# demo0920.net
KiCad netlist of a schematic drawn in Altium Designer
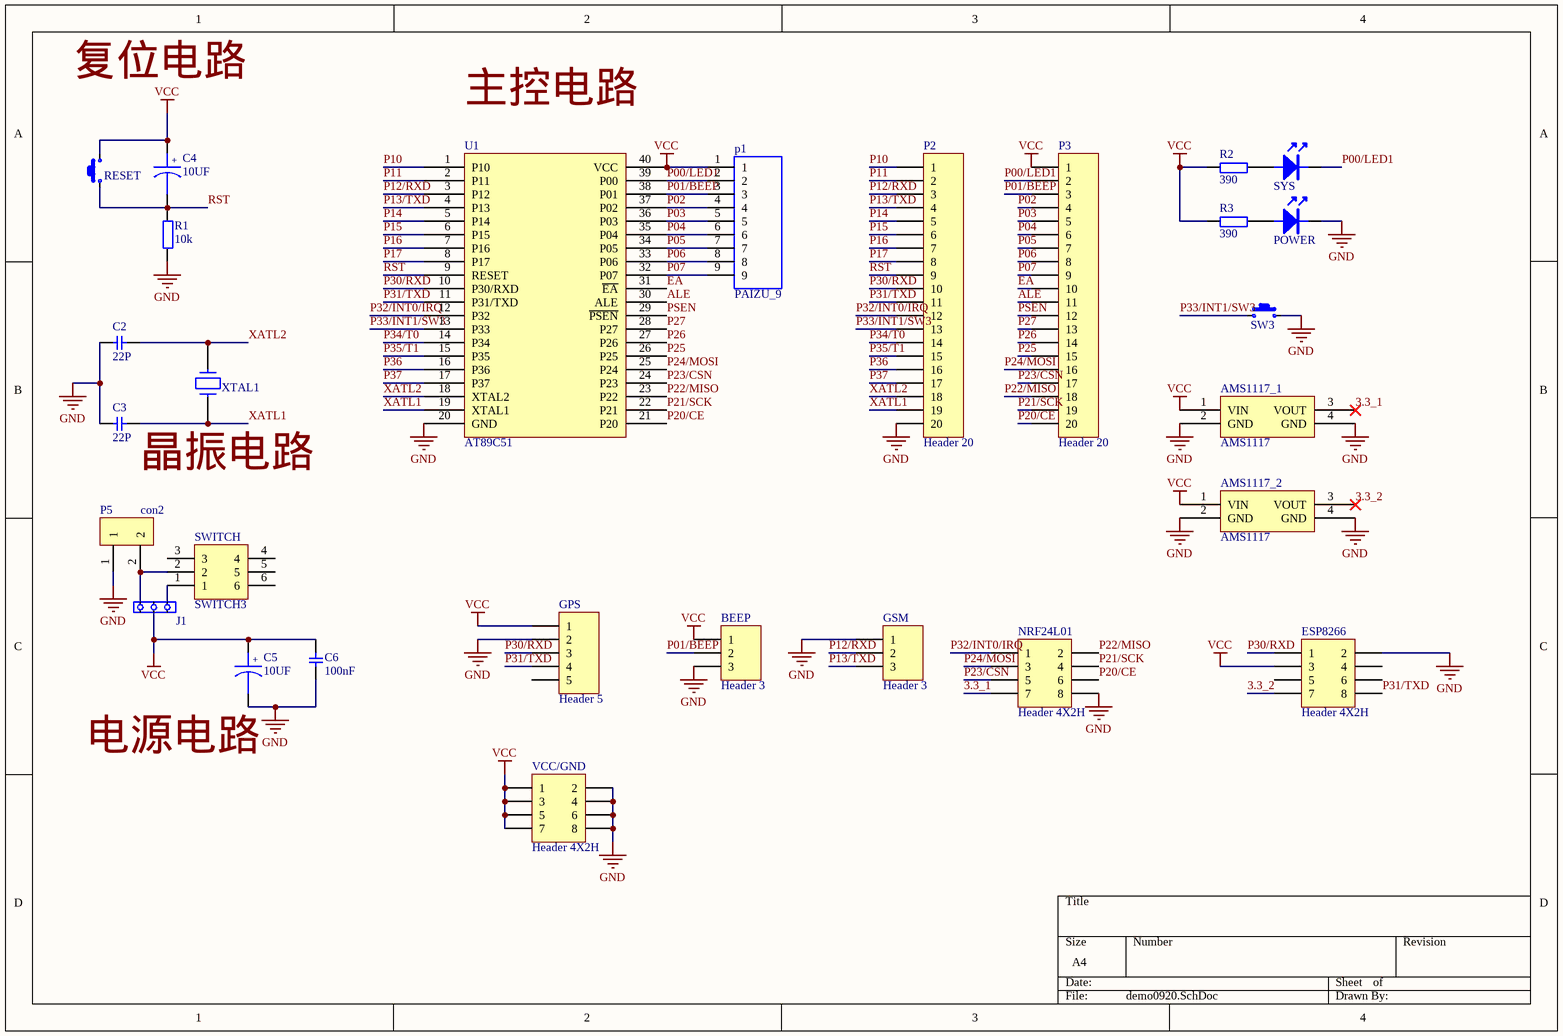
[diagram p0: demo0920.SchDoc]

(export (version "E")
  (design (tool "Eeschema 10.0.6"))
  (components
    (comp (ref "AMS1117_1") (value "AMS1117") (footprint "AMS1117") (libsource (lib "SQ-1") (part "AMS1117")))
    (comp (ref "AMS1117_2") (value "AMS1117") (footprint "AMS1117") (libsource (lib "SQ-1") (part "AMS1117")))
    (comp (ref "BEEP")
      (value "Header 3")
      (footprint "HDR1X3")
      (description "Header, 3-Pin")
      (fields (field (name "PUBLISHER") "Altium Limited"))
      (libsource (lib "Miscellaneous Connectors") (part "Header 3"))
    )
    (comp (ref "C2")
      (value "22")
      (footprint "0805C")
      (description "C")
      (fields (field (name "ALTIUM_UNNAMED_1") "22P"))
      (libsource (lib "SQ-1") (part "CAP"))
    )
    (comp (ref "C3")
      (value "22")
      (footprint "0805C")
      (description "C")
      (fields (field (name "ALTIUM_UNNAMED_1") "22P"))
      (libsource (lib "SQ-1") (part "CAP"))
    )
    (comp (ref "C4")
      (value "CAPD")
      (footprint "RB470U")
      (fields (field (name "ALTIUM_UNNAMED_1") "10UF"))
      (libsource (lib "SQ-1") (part "CAPD"))
    )
    (comp (ref "C5")
      (value "CAPD")
      (footprint "RB470U")
      (fields (field (name "ALTIUM_UNNAMED_1") "10UF"))
      (libsource (lib "SQ-1") (part "CAPD"))
    )
    (comp (ref "C6")
      (value "22")
      (footprint "0805C")
      (description "C")
      (fields (field (name "ALTIUM_UNNAMED_1") "100nF"))
      (libsource (lib "SQ-1") (part "CAP"))
    )
    (comp (ref "ESP8266")
      (value "Header 4X2H")
      (footprint "HDR2X4H")
      (description "Header, 4-Pin, Dual row, Right Angle")
      (fields (field (name "PUBLISHER") "Altium Limited"))
      (libsource (lib "SQ-1") (part "Header 4X2H"))
    )
    (comp (ref "GPS")
      (value "Header 5")
      (footprint "HDR1X5")
      (description "Header, 5-Pin")
      (fields (field (name "PUBLISHER") "Altium Limited"))
      (libsource (lib "Miscellaneous Connectors") (part "Header 5"))
    )
    (comp (ref "GSM")
      (value "Header 3")
      (footprint "HDR1X3")
      (description "Header, 3-Pin")
      (fields (field (name "PUBLISHER") "Altium Limited"))
      (libsource (lib "Miscellaneous Connectors") (part "Header 3"))
    )
    (comp (ref "J1") (value "Select") (footprint "CON3") (libsource (lib "SQ-1") (part "JUMP3")))
    (comp (ref "NRF24L01")
      (value "Header 4X2H")
      (footprint "HDR2X4H")
      (description "Header, 4-Pin, Dual row, Right Angle")
      (fields (field (name "PUBLISHER") "Altium Limited"))
      (libsource (lib "SQ-1") (part "Header 4X2H"))
    )
    (comp (ref "p1") (value "PAIZU_9") (footprint "PAIZU_9") (libsource (lib "SQ-1") (part "PAIZU_9")))
    (comp (ref "P2")
      (value "Header 20")
      (footprint "HDR1X20")
      (description "Header, 20-Pin")
      (fields (field (name "PUBLISHER") "Altium Limited"))
      (libsource (lib "SQ-1") (part "Header 20"))
    )
    (comp (ref "P3")
      (value "Header 20")
      (footprint "HDR1X20")
      (description "Header, 20-Pin")
      (fields (field (name "PUBLISHER") "Altium Limited"))
      (libsource (lib "SQ-1") (part "Header 20"))
    )
    (comp (ref "P5") (value "con2") (footprint "CON2") (libsource (lib "SQ-1") (part "con2")))
    (comp (ref "POWER") (value "LED") (footprint "0805-LED") (libsource (lib "SQ-1") (part "LED")))
    (comp (ref "R1") (value "10k") (footprint "0805") (description "R?") (libsource (lib "SQ-1") (part "R1")))
    (comp (ref "R2") (value "390") (footprint "0805") (description "R?") (libsource (lib "SQ-1") (part "R1")))
    (comp (ref "R3") (value "390") (footprint "0805") (description "R?") (libsource (lib "SQ-1") (part "R1")))
    (comp (ref "RESET") (value "SW") (footprint "SWD") (libsource (lib "SQ-1") (part "SW")))
    (comp (ref "SW3") (value "SW") (footprint "SWD") (libsource (lib "SQ-1") (part "SW")))
    (comp (ref "SWITCH") (value "SWITCH3") (footprint "SWITCH3") (libsource (lib "SQ-1") (part "SWITCH3")))
    (comp (ref "SYS") (value "LED") (footprint "0805-LED") (libsource (lib "SQ-1") (part "LED")))
    (comp (ref "U1") (value "AT89C51") (footprint "DIP40紧锁座") (libsource (lib "SQ-1") (part "AT89C51")))
    (comp (ref "VCC/GND")
      (value "Header 4X2H")
      (footprint "HDR2X4H")
      (description "Header, 4-Pin, Dual row, Right Angle")
      (fields (field (name "PUBLISHER") "Altium Limited"))
      (libsource (lib "SQ-1") (part "Header 4X2H"))
    )
    (comp (ref "XTAL1") (value "CRYSTAL") (footprint "XTAL") (libsource (lib "SQ-1") (part "CRYSTAL")))
  )
  (nets
    (net (code "1") (name "/3.3_1") (class "Default")
      (node (ref "AMS1117_1") (pin "3") (pinfunction "VOUT_3") (pintype "passive"))
      (node (ref "NRF24L01") (pin "7") (pinfunction "7_7") (pintype "passive"))
    )
    (net (code "2") (name "/3.3_2") (class "Default")
      (node (ref "AMS1117_2") (pin "3") (pinfunction "VOUT_3") (pintype "passive"))
      (node (ref "ESP8266") (pin "7") (pinfunction "7_7") (pintype "passive"))
    )
    (net (code "3") (name "/ALE") (class "Default")
      (node (ref "P3") (pin "11") (pinfunction "11_11") (pintype "passive"))
      (node (ref "U1") (pin "30") (pinfunction "ALE_30") (pintype "passive"))
    )
    (net (code "4") (name "/EA") (class "Default")
      (node (ref "P3") (pin "10") (pinfunction "10_10") (pintype "passive"))
      (node (ref "U1") (pin "31") (pinfunction "~{EA}_31") (pintype "passive"))
    )
    (net (code "5") (name "/P00{slash}LED1") (class "Default")
      (node (ref "P3") (pin "2") (pinfunction "2_2") (pintype "passive"))
      (node (ref "SYS") (pin "2") (pinfunction "2_2") (pintype "passive"))
      (node (ref "U1") (pin "39") (pinfunction "P00_39") (pintype "passive"))
      (node (ref "p1") (pin "2") (pinfunction "2_2") (pintype "passive"))
    )
    (net (code "6") (name "/P01{slash}BEEP") (class "Default")
      (node (ref "BEEP") (pin "2") (pinfunction "2_2") (pintype "passive"))
      (node (ref "P3") (pin "3") (pinfunction "3_3") (pintype "passive"))
      (node (ref "U1") (pin "38") (pinfunction "P01_38") (pintype "passive"))
      (node (ref "p1") (pin "3") (pinfunction "3_3") (pintype "passive"))
    )
    (net (code "7") (name "/P02") (class "Default")
      (node (ref "P3") (pin "4") (pinfunction "4_4") (pintype "passive"))
      (node (ref "U1") (pin "37") (pinfunction "P02_37") (pintype "passive"))
      (node (ref "p1") (pin "4") (pinfunction "4_4") (pintype "passive"))
    )
    (net (code "8") (name "/P03") (class "Default")
      (node (ref "P3") (pin "5") (pinfunction "5_5") (pintype "passive"))
      (node (ref "U1") (pin "36") (pinfunction "P03_36") (pintype "passive"))
      (node (ref "p1") (pin "5") (pinfunction "5_5") (pintype "passive"))
    )
    (net (code "9") (name "/P04") (class "Default")
      (node (ref "P3") (pin "6") (pinfunction "6_6") (pintype "passive"))
      (node (ref "U1") (pin "35") (pinfunction "P04_35") (pintype "passive"))
      (node (ref "p1") (pin "6") (pinfunction "6_6") (pintype "passive"))
    )
    (net (code "10") (name "/P05") (class "Default")
      (node (ref "P3") (pin "7") (pinfunction "7_7") (pintype "passive"))
      (node (ref "U1") (pin "34") (pinfunction "P05_34") (pintype "passive"))
      (node (ref "p1") (pin "7") (pinfunction "7_7") (pintype "passive"))
    )
    (net (code "11") (name "/P06") (class "Default")
      (node (ref "P3") (pin "8") (pinfunction "8_8") (pintype "passive"))
      (node (ref "U1") (pin "33") (pinfunction "P06_33") (pintype "passive"))
      (node (ref "p1") (pin "8") (pinfunction "8_8") (pintype "passive"))
    )
    (net (code "12") (name "/P07") (class "Default")
      (node (ref "P3") (pin "9") (pinfunction "9_9") (pintype "passive"))
      (node (ref "U1") (pin "32") (pinfunction "P07_32") (pintype "passive"))
      (node (ref "p1") (pin "9") (pinfunction "9_9") (pintype "passive"))
    )
    (net (code "13") (name "/P10") (class "Default")
      (node (ref "P2") (pin "1") (pinfunction "1_1") (pintype "passive"))
      (node (ref "U1") (pin "1") (pinfunction "P10_1") (pintype "passive"))
    )
    (net (code "14") (name "/P11") (class "Default")
      (node (ref "P2") (pin "2") (pinfunction "2_2") (pintype "passive"))
      (node (ref "U1") (pin "2") (pinfunction "P11_2") (pintype "passive"))
    )
    (net (code "15") (name "/P12{slash}RXD") (class "Default")
      (node (ref "GSM") (pin "2") (pinfunction "2_2") (pintype "passive"))
      (node (ref "P2") (pin "3") (pinfunction "3_3") (pintype "passive"))
      (node (ref "U1") (pin "3") (pinfunction "P12_3") (pintype "passive"))
    )
    (net (code "16") (name "/P13{slash}TXD") (class "Default")
      (node (ref "GSM") (pin "3") (pinfunction "3_3") (pintype "passive"))
      (node (ref "P2") (pin "4") (pinfunction "4_4") (pintype "passive"))
      (node (ref "U1") (pin "4") (pinfunction "P13_4") (pintype "passive"))
    )
    (net (code "17") (name "/P14") (class "Default")
      (node (ref "P2") (pin "5") (pinfunction "5_5") (pintype "passive"))
      (node (ref "U1") (pin "5") (pinfunction "P14_5") (pintype "passive"))
    )
    (net (code "18") (name "/P15") (class "Default")
      (node (ref "P2") (pin "6") (pinfunction "6_6") (pintype "passive"))
      (node (ref "U1") (pin "6") (pinfunction "P15_6") (pintype "passive"))
    )
    (net (code "19") (name "/P16") (class "Default")
      (node (ref "P2") (pin "7") (pinfunction "7_7") (pintype "passive"))
      (node (ref "U1") (pin "7") (pinfunction "P16_7") (pintype "passive"))
    )
    (net (code "20") (name "/P17") (class "Default")
      (node (ref "P2") (pin "8") (pinfunction "8_8") (pintype "passive"))
      (node (ref "U1") (pin "8") (pinfunction "P17_8") (pintype "passive"))
    )
    (net (code "21") (name "/P20{slash}CE") (class "Default")
      (node (ref "NRF24L01") (pin "6") (pinfunction "6_6") (pintype "passive"))
      (node (ref "P3") (pin "20") (pinfunction "20_20") (pintype "passive"))
      (node (ref "U1") (pin "21") (pinfunction "P20_21") (pintype "passive"))
    )
    (net (code "22") (name "/P21{slash}SCK") (class "Default")
      (node (ref "NRF24L01") (pin "4") (pinfunction "4_4") (pintype "passive"))
      (node (ref "P3") (pin "19") (pinfunction "19_19") (pintype "passive"))
      (node (ref "U1") (pin "22") (pinfunction "P21_22") (pintype "passive"))
    )
    (net (code "23") (name "/P22{slash}MISO") (class "Default")
      (node (ref "NRF24L01") (pin "2") (pinfunction "2_2") (pintype "passive"))
      (node (ref "P3") (pin "18") (pinfunction "18_18") (pintype "passive"))
      (node (ref "U1") (pin "23") (pinfunction "P22_23") (pintype "passive"))
    )
    (net (code "24") (name "/P23{slash}CSN") (class "Default")
      (node (ref "NRF24L01") (pin "5") (pinfunction "5_5") (pintype "passive"))
      (node (ref "P3") (pin "17") (pinfunction "17_17") (pintype "passive"))
      (node (ref "U1") (pin "24") (pinfunction "P23_24") (pintype "passive"))
    )
    (net (code "25") (name "/P24{slash}MOSI") (class "Default")
      (node (ref "NRF24L01") (pin "3") (pinfunction "3_3") (pintype "passive"))
      (node (ref "P3") (pin "16") (pinfunction "16_16") (pintype "passive"))
      (node (ref "U1") (pin "25") (pinfunction "P24_25") (pintype "passive"))
    )
    (net (code "26") (name "/P25") (class "Default")
      (node (ref "P3") (pin "15") (pinfunction "15_15") (pintype "passive"))
      (node (ref "U1") (pin "26") (pinfunction "P25_26") (pintype "passive"))
    )
    (net (code "27") (name "/P26") (class "Default")
      (node (ref "P3") (pin "14") (pinfunction "14_14") (pintype "passive"))
      (node (ref "U1") (pin "27") (pinfunction "P26_27") (pintype "passive"))
    )
    (net (code "28") (name "/P27") (class "Default")
      (node (ref "P3") (pin "13") (pinfunction "13_13") (pintype "passive"))
      (node (ref "U1") (pin "28") (pinfunction "P27_28") (pintype "passive"))
    )
    (net (code "29") (name "/P30{slash}RXD") (class "Default")
      (node (ref "ESP8266") (pin "1") (pinfunction "1_1") (pintype "passive"))
      (node (ref "GPS") (pin "3") (pinfunction "3_3") (pintype "passive"))
      (node (ref "P2") (pin "10") (pinfunction "10_10") (pintype "passive"))
      (node (ref "U1") (pin "10") (pinfunction "P30/RXD_10") (pintype "passive"))
    )
    (net (code "30") (name "/P31{slash}TXD") (class "Default")
      (node (ref "ESP8266") (pin "8") (pinfunction "8_8") (pintype "passive"))
      (node (ref "GPS") (pin "4") (pinfunction "4_4") (pintype "passive"))
      (node (ref "P2") (pin "11") (pinfunction "11_11") (pintype "passive"))
      (node (ref "U1") (pin "11") (pinfunction "P31/TXD_11") (pintype "passive"))
    )
    (net (code "31") (name "/P32{slash}INT0{slash}IRQ") (class "Default")
      (node (ref "NRF24L01") (pin "1") (pinfunction "1_1") (pintype "passive"))
      (node (ref "P2") (pin "12") (pinfunction "12_12") (pintype "passive"))
      (node (ref "U1") (pin "12") (pinfunction "P32_12") (pintype "passive"))
    )
    (net (code "32") (name "/P33{slash}INT1{slash}SW3") (class "Default")
      (node (ref "P2") (pin "13") (pinfunction "13_13") (pintype "passive"))
      (node (ref "SW3") (pin "1") (pinfunction "1_1") (pintype "passive"))
      (node (ref "U1") (pin "13") (pinfunction "P33_13") (pintype "passive"))
    )
    (net (code "33") (name "/P34{slash}T0") (class "Default")
      (node (ref "P2") (pin "14") (pinfunction "14_14") (pintype "passive"))
      (node (ref "U1") (pin "14") (pinfunction "P34_14") (pintype "passive"))
    )
    (net (code "34") (name "/P35{slash}T1") (class "Default")
      (node (ref "P2") (pin "15") (pinfunction "15_15") (pintype "passive"))
      (node (ref "U1") (pin "15") (pinfunction "P35_15") (pintype "passive"))
    )
    (net (code "35") (name "/P36") (class "Default")
      (node (ref "P2") (pin "16") (pinfunction "16_16") (pintype "passive"))
      (node (ref "U1") (pin "16") (pinfunction "P36_16") (pintype "passive"))
    )
    (net (code "36") (name "/P37") (class "Default")
      (node (ref "P2") (pin "17") (pinfunction "17_17") (pintype "passive"))
      (node (ref "U1") (pin "17") (pinfunction "P37_17") (pintype "passive"))
    )
    (net (code "37") (name "/PSEN") (class "Default")
      (node (ref "P3") (pin "12") (pinfunction "12_12") (pintype "passive"))
      (node (ref "U1") (pin "29") (pinfunction "~{PSEN}_29") (pintype "passive"))
    )
    (net (code "38") (name "/RST") (class "Default")
      (node (ref "C4") (pin "2") (pinfunction "2_2") (pintype "passive"))
      (node (ref "P2") (pin "9") (pinfunction "9_9") (pintype "passive"))
      (node (ref "R1") (pin "2") (pinfunction "2_2") (pintype "passive"))
      (node (ref "RESET") (pin "1") (pinfunction "1_1") (pintype "passive"))
      (node (ref "U1") (pin "9") (pinfunction "RESET_9") (pintype "passive"))
    )
    (net (code "39") (name "/XATL1") (class "Default")
      (node (ref "C3") (pin "2") (pinfunction "2_2") (pintype "passive"))
      (node (ref "P2") (pin "19") (pinfunction "19_19") (pintype "passive"))
      (node (ref "U1") (pin "19") (pinfunction "XTAL1_19") (pintype "passive"))
      (node (ref "XTAL1") (pin "1") (pinfunction "1_1") (pintype "passive"))
    )
    (net (code "40") (name "/XATL2") (class "Default")
      (node (ref "C2") (pin "2") (pinfunction "2_2") (pintype "passive"))
      (node (ref "P2") (pin "18") (pinfunction "18_18") (pintype "passive"))
      (node (ref "U1") (pin "18") (pinfunction "XTAL2_18") (pintype "passive"))
      (node (ref "XTAL1") (pin "2") (pinfunction "2_2") (pintype "passive"))
    )
    (net (code "41") (name "GND") (class "Default")
      (node (ref "AMS1117_1") (pin "2") (pinfunction "GND_2") (pintype "passive"))
      (node (ref "AMS1117_1") (pin "4") (pinfunction "GND_4") (pintype "passive"))
      (node (ref "AMS1117_2") (pin "2") (pinfunction "GND_2") (pintype "passive"))
      (node (ref "AMS1117_2") (pin "4") (pinfunction "GND_4") (pintype "passive"))
      (node (ref "BEEP") (pin "3") (pinfunction "3_3") (pintype "passive"))
      (node (ref "C2") (pin "1") (pinfunction "2_1") (pintype "passive"))
      (node (ref "C3") (pin "1") (pinfunction "2_1") (pintype "passive"))
      (node (ref "C5") (pin "2") (pinfunction "2_2") (pintype "passive"))
      (node (ref "C6") (pin "1") (pinfunction "2_1") (pintype "passive"))
      (node (ref "ESP8266") (pin "2") (pinfunction "2_2") (pintype "passive"))
      (node (ref "GPS") (pin "2") (pinfunction "2_2") (pintype "passive"))
      (node (ref "GSM") (pin "1") (pinfunction "1_1") (pintype "passive"))
      (node (ref "NRF24L01") (pin "8") (pinfunction "8_8") (pintype "passive"))
      (node (ref "P2") (pin "20") (pinfunction "20_20") (pintype "passive"))
      (node (ref "P5") (pin "1") (pinfunction "1_1") (pintype "passive"))
      (node (ref "POWER") (pin "2") (pinfunction "2_2") (pintype "passive"))
      (node (ref "R1") (pin "1") (pinfunction "1_1") (pintype "passive"))
      (node (ref "SW3") (pin "2") (pinfunction "2_2") (pintype "passive"))
      (node (ref "U1") (pin "20") (pinfunction "GND_20") (pintype "passive"))
      (node (ref "VCC/GND") (pin "2") (pinfunction "2_2") (pintype "passive"))
      (node (ref "VCC/GND") (pin "4") (pinfunction "4_4") (pintype "passive"))
      (node (ref "VCC/GND") (pin "6") (pinfunction "6_6") (pintype "passive"))
      (node (ref "VCC/GND") (pin "8") (pinfunction "8_8") (pintype "passive"))
    )
    (net (code "42") (name "Net-(J1-Pad1)") (class "Default")
      (node (ref "J1") (pin "1") (pinfunction "1_1") (pintype "passive"))
      (node (ref "SWITCH") (pin "1") (pinfunction "1_1") (pintype "passive"))
    )
    (net (code "43") (name "Net-(J1-Pad3)") (class "Default")
      (node (ref "J1") (pin "3") (pinfunction "3_3") (pintype "passive"))
      (node (ref "P5") (pin "2") (pinfunction "2_2") (pintype "passive"))
      (node (ref "SWITCH") (pin "2") (pinfunction "2_2") (pintype "passive"))
    )
    (net (code "44") (name "Net-(POWER-Pad1)") (class "Default")
      (node (ref "POWER") (pin "1") (pinfunction "1_1") (pintype "passive"))
      (node (ref "R3") (pin "2") (pinfunction "2_2") (pintype "passive"))
    )
    (net (code "45") (name "Net-(R2-Pad2)") (class "Default")
      (node (ref "R2") (pin "2") (pinfunction "2_2") (pintype "passive"))
      (node (ref "SYS") (pin "1") (pinfunction "1_1") (pintype "passive"))
    )
    (net (code "46") (name "VCC") (class "Default")
      (node (ref "AMS1117_1") (pin "1") (pinfunction "VIN_1") (pintype "passive"))
      (node (ref "AMS1117_2") (pin "1") (pinfunction "VIN_1") (pintype "passive"))
      (node (ref "BEEP") (pin "1") (pinfunction "1_1") (pintype "passive"))
      (node (ref "C4") (pin "1") (pinfunction "1_1") (pintype "passive"))
      (node (ref "C5") (pin "1") (pinfunction "1_1") (pintype "passive"))
      (node (ref "C6") (pin "2") (pinfunction "2_2") (pintype "passive"))
      (node (ref "ESP8266") (pin "3") (pinfunction "3_3") (pintype "passive"))
      (node (ref "GPS") (pin "1") (pinfunction "1_1") (pintype "passive"))
      (node (ref "J1") (pin "2") (pinfunction "2_2") (pintype "passive"))
      (node (ref "P3") (pin "1") (pinfunction "1_1") (pintype "passive"))
      (node (ref "R2") (pin "1") (pinfunction "1_1") (pintype "passive"))
      (node (ref "R3") (pin "1") (pinfunction "1_1") (pintype "passive"))
      (node (ref "RESET") (pin "2") (pinfunction "2_2") (pintype "passive"))
      (node (ref "U1") (pin "40") (pinfunction "VCC_40") (pintype "passive"))
      (node (ref "VCC/GND") (pin "1") (pinfunction "1_1") (pintype "passive"))
      (node (ref "VCC/GND") (pin "3") (pinfunction "3_3") (pintype "passive"))
      (node (ref "VCC/GND") (pin "5") (pinfunction "5_5") (pintype "passive"))
      (node (ref "VCC/GND") (pin "7") (pinfunction "7_7") (pintype "passive"))
      (node (ref "p1") (pin "1") (pinfunction "1_1") (pintype "passive"))
    )
    (net (code "47") (name "unconnected-(ESP8266-Pad4)") (class "Default")
      (node (ref "ESP8266") (pin "4") (pinfunction "4_4") (pintype "passive"))
    )
    (net (code "48") (name "unconnected-(ESP8266-Pad5)") (class "Default")
      (node (ref "ESP8266") (pin "5") (pinfunction "5_5") (pintype "passive"))
    )
    (net (code "49") (name "unconnected-(ESP8266-Pad6)") (class "Default")
      (node (ref "ESP8266") (pin "6") (pinfunction "6_6") (pintype "passive"))
    )
    (net (code "50") (name "unconnected-(GPS-Pad5)") (class "Default")
      (node (ref "GPS") (pin "5") (pinfunction "5_5") (pintype "passive"))
    )
    (net (code "51") (name "unconnected-(SWITCH-Pad3)") (class "Default")
      (node (ref "SWITCH") (pin "3") (pinfunction "3_3") (pintype "passive"))
    )
    (net (code "52") (name "unconnected-(SWITCH-Pad4)") (class "Default")
      (node (ref "SWITCH") (pin "4") (pinfunction "4_4") (pintype "passive"))
    )
    (net (code "53") (name "unconnected-(SWITCH-Pad5)") (class "Default")
      (node (ref "SWITCH") (pin "5") (pinfunction "5_5") (pintype "passive"))
    )
    (net (code "54") (name "unconnected-(SWITCH-Pad6)") (class "Default")
      (node (ref "SWITCH") (pin "6") (pinfunction "6_6") (pintype "passive"))
    )
  )
)
